# 01-main.net
KiCad netlist of a schematic drawn in EAGLE
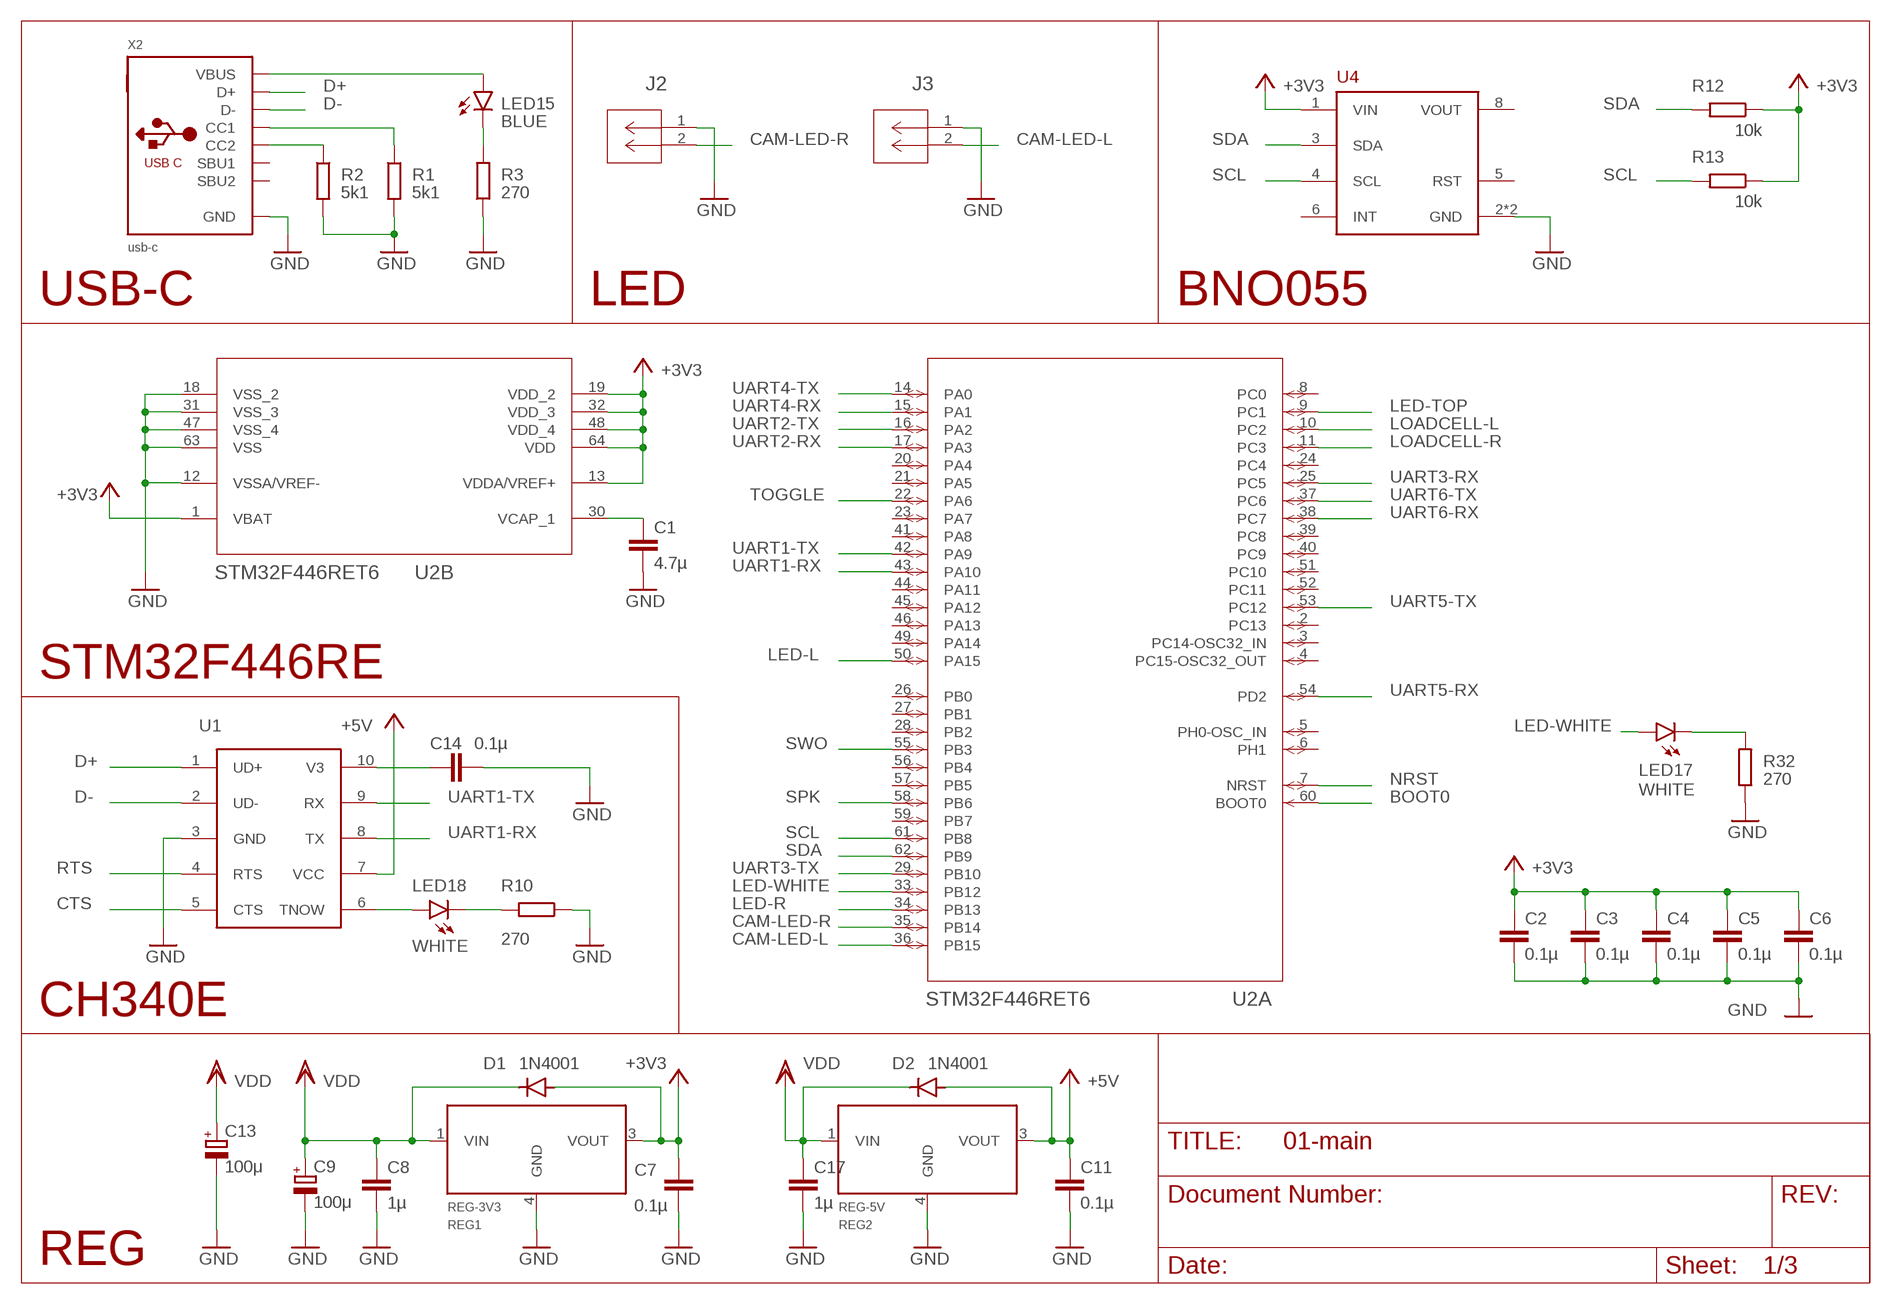
[diagram p0: schematic, sheet 1]
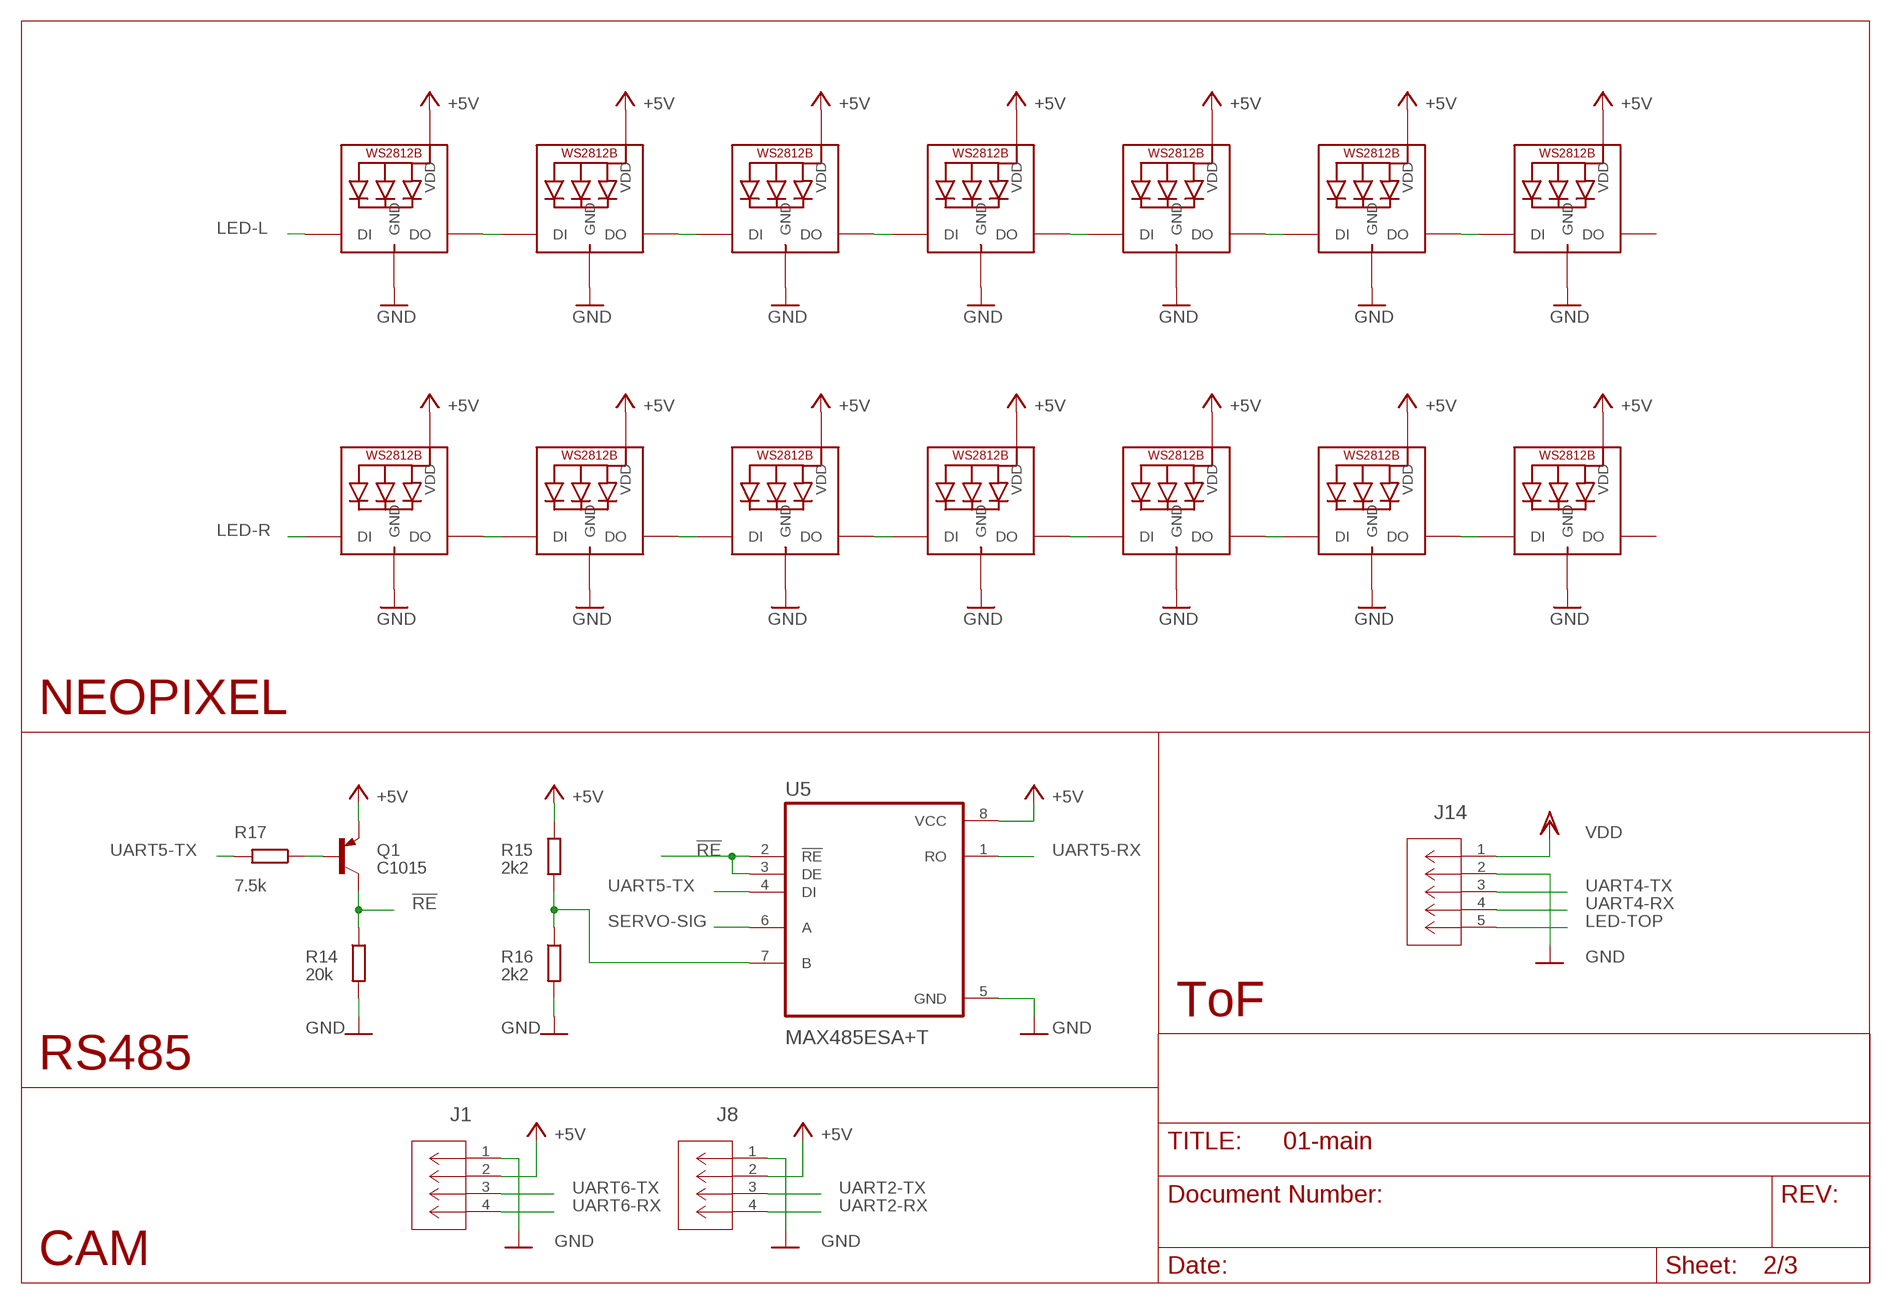
[diagram p1: schematic, sheet 2]
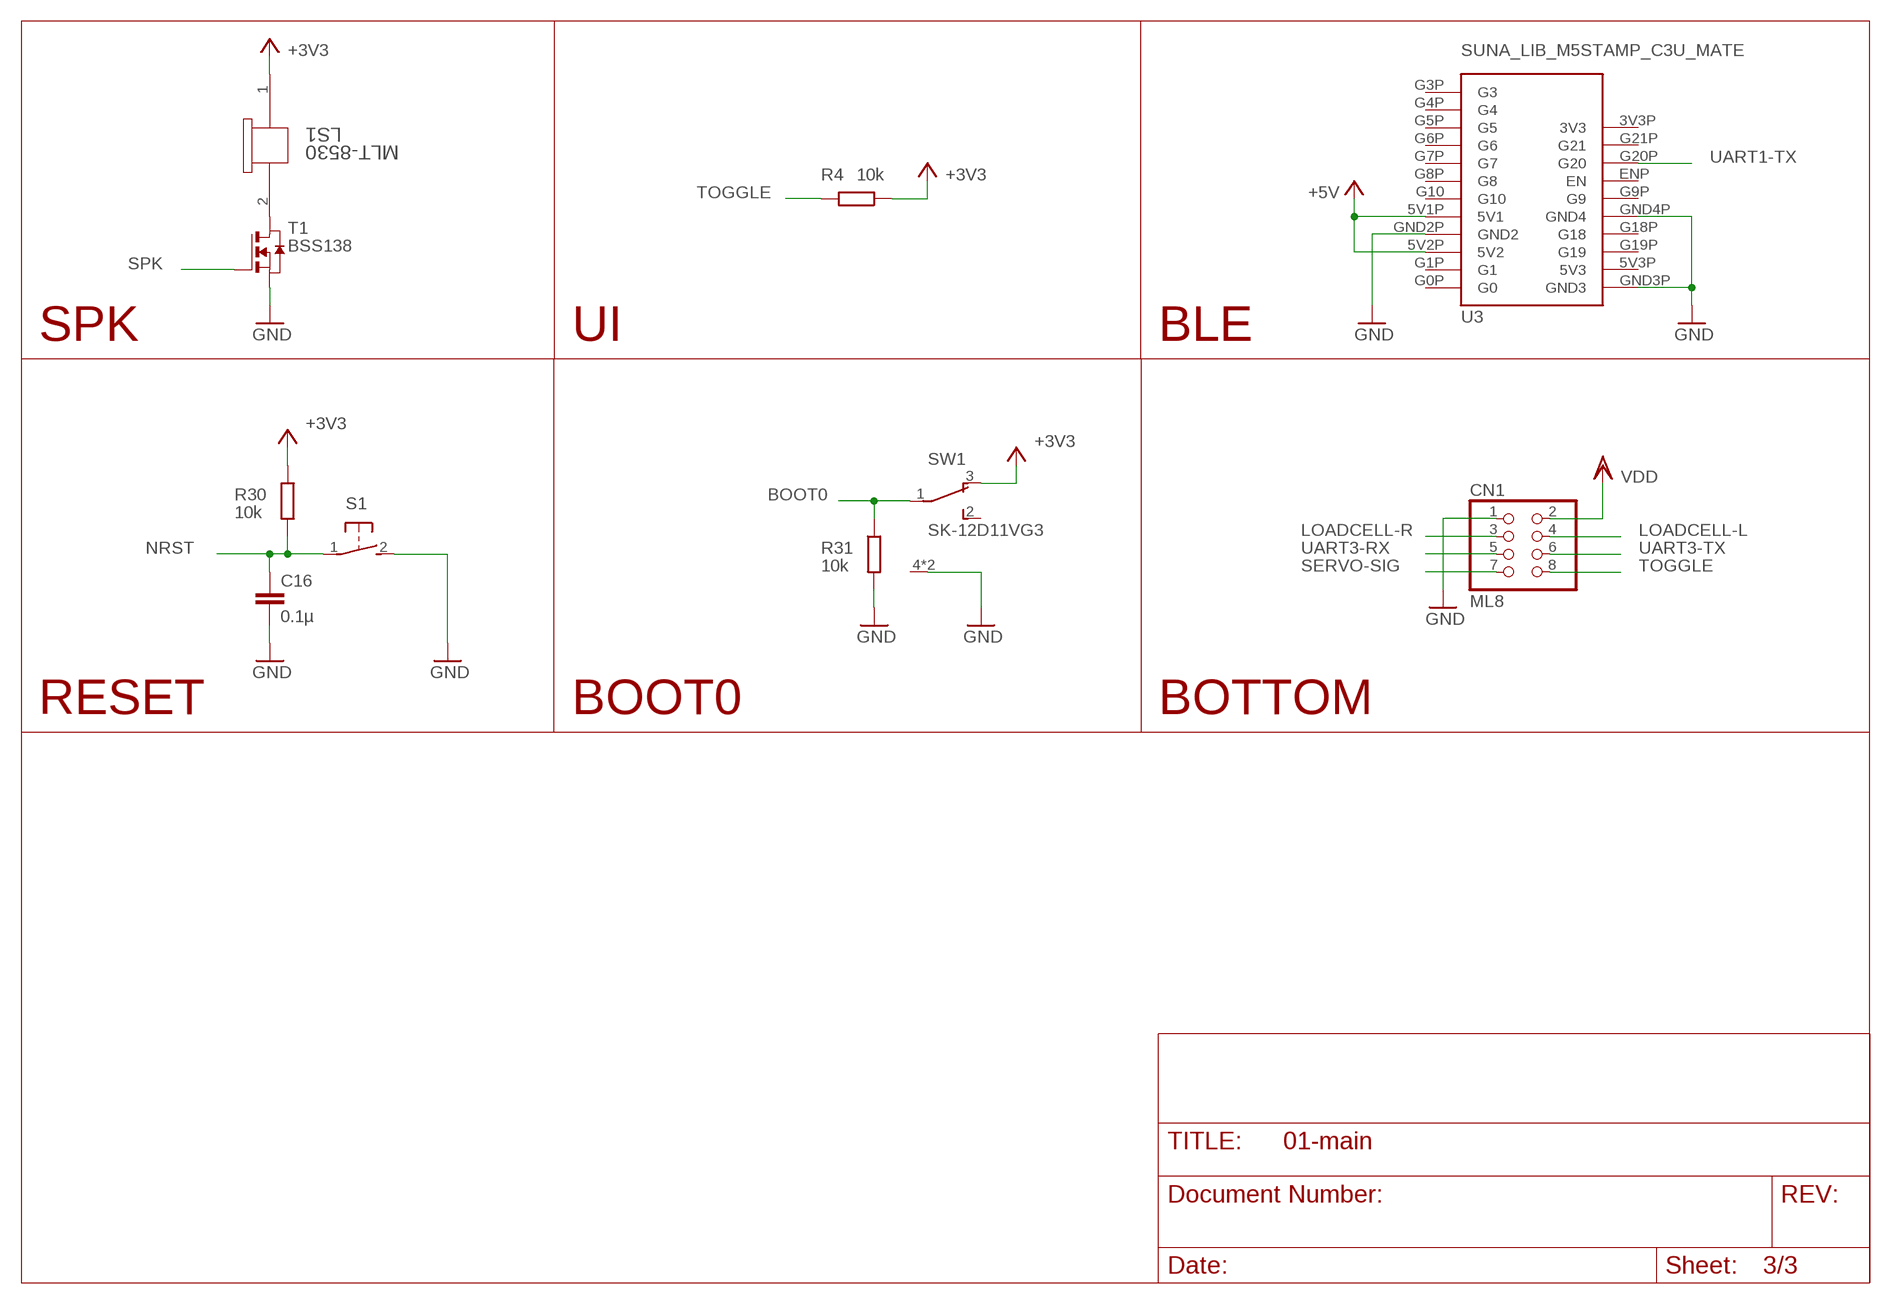
[diagram p2: schematic, sheet 3]

(export (version "E")
  (design (tool "Eeschema 10.0.6"))
  (components
    (comp (ref "J1")
      (value "22057045")
      (footprint "eagle-import:CON_22057045_MOL")
      (fields (field (name "COPYRIGHT") "Copyright (C) 2022 Ultra Librarian. All rights reserved."))
      (libsource (lib "eagle-import") (part "22057045"))
    )
    (comp (ref "J8")
      (value "22057045")
      (footprint "eagle-import:CON_22057045_MOL")
      (fields (field (name "COPYRIGHT") "Copyright (C) 2022 Ultra Librarian. All rights reserved."))
      (libsource (lib "eagle-import") (part "22057045"))
    )
    (comp (ref "J14")
      (value "22057055")
      (footprint "eagle-import:CON_22057055_MOL")
      (fields (field (name "COPYRIGHT") "Copyright (C) 2022 Ultra Librarian. All rights reserved."))
      (libsource (lib "eagle-import") (part "22057055"))
    )
    (comp (ref "LED1")
      (value "WS2812B_2020")
      (footprint "eagle-import:WS2812B_2020")
      (libsource (lib "eagle-import") (part "WS2812B_2020"))
    )
    (comp (ref "LED2")
      (value "WS2812B_2020")
      (footprint "eagle-import:WS2812B_2020")
      (libsource (lib "eagle-import") (part "WS2812B_2020"))
    )
    (comp (ref "LED3")
      (value "WS2812B_2020")
      (footprint "eagle-import:WS2812B_2020")
      (libsource (lib "eagle-import") (part "WS2812B_2020"))
    )
    (comp (ref "LED4")
      (value "WS2812B_2020")
      (footprint "eagle-import:WS2812B_2020")
      (libsource (lib "eagle-import") (part "WS2812B_2020"))
    )
    (comp (ref "LED5")
      (value "WS2812B_2020")
      (footprint "eagle-import:WS2812B_2020")
      (libsource (lib "eagle-import") (part "WS2812B_2020"))
    )
    (comp (ref "LED6")
      (value "WS2812B_2020")
      (footprint "eagle-import:WS2812B_2020")
      (libsource (lib "eagle-import") (part "WS2812B_2020"))
    )
    (comp (ref "LED7")
      (value "WS2812B_2020")
      (footprint "eagle-import:WS2812B_2020")
      (libsource (lib "eagle-import") (part "WS2812B_2020"))
    )
    (comp (ref "LED8")
      (value "WS2812B_2020")
      (footprint "eagle-import:WS2812B_2020")
      (libsource (lib "eagle-import") (part "WS2812B_2020"))
    )
    (comp (ref "LED9")
      (value "WS2812B_2020")
      (footprint "eagle-import:WS2812B_2020")
      (libsource (lib "eagle-import") (part "WS2812B_2020"))
    )
    (comp (ref "LED10")
      (value "WS2812B_2020")
      (footprint "eagle-import:WS2812B_2020")
      (libsource (lib "eagle-import") (part "WS2812B_2020"))
    )
    (comp (ref "LED11")
      (value "WS2812B_2020")
      (footprint "eagle-import:WS2812B_2020")
      (libsource (lib "eagle-import") (part "WS2812B_2020"))
    )
    (comp (ref "LED12")
      (value "WS2812B_2020")
      (footprint "eagle-import:WS2812B_2020")
      (libsource (lib "eagle-import") (part "WS2812B_2020"))
    )
    (comp (ref "LED13")
      (value "WS2812B_2020")
      (footprint "eagle-import:WS2812B_2020")
      (libsource (lib "eagle-import") (part "WS2812B_2020"))
    )
    (comp (ref "LED14")
      (value "WS2812B_2020")
      (footprint "eagle-import:WS2812B_2020")
      (libsource (lib "eagle-import") (part "WS2812B_2020"))
    )
    (comp (ref "Q1")
      (value "C1015")
      (footprint "eagle-import:SOT23")
      (libsource (lib "eagle-import") (part "BCX71SMD"))
    )
    (comp (ref "R14")
      (value "20k")
      (footprint "eagle-import:R0402")
      (libsource (lib "eagle-import") (part "R-EU_R0402"))
    )
    (comp (ref "R15")
      (value "2k2")
      (footprint "eagle-import:R0402")
      (libsource (lib "eagle-import") (part "R-EU_R0402"))
    )
    (comp (ref "R16")
      (value "2k2")
      (footprint "eagle-import:R0402")
      (libsource (lib "eagle-import") (part "R-EU_R0402"))
    )
    (comp (ref "R17")
      (value "7.5k")
      (footprint "eagle-import:R0402")
      (libsource (lib "eagle-import") (part "R-EU_R0402"))
    )
    (comp (ref "U5")
      (value "MAX485ESA+T")
      (footprint "eagle-import:SOIC127P600X175-8N")
      (fields (field (name "MF") "Maxim Integrated") (field (name "MP") "MAX485ESA"))
      (libsource (lib "eagle-import") (part "MAX485ESA+T"))
    )
    (comp (ref "C1")
      (value "4.7µ")
      (footprint "eagle-import:C0603")
      (libsource (lib "eagle-import") (part "C-EUC0603"))
    )
    (comp (ref "C2")
      (value "0.1µ")
      (footprint "eagle-import:C0603")
      (libsource (lib "eagle-import") (part "C-EUC0603"))
    )
    (comp (ref "C3")
      (value "0.1µ")
      (footprint "eagle-import:C0603")
      (libsource (lib "eagle-import") (part "C-EUC0603"))
    )
    (comp (ref "C4")
      (value "0.1µ")
      (footprint "eagle-import:C0603")
      (libsource (lib "eagle-import") (part "C-EUC0603"))
    )
    (comp (ref "C5")
      (value "0.1µ")
      (footprint "eagle-import:C0603")
      (libsource (lib "eagle-import") (part "C-EUC0603"))
    )
    (comp (ref "C6")
      (value "0.1µ")
      (footprint "eagle-import:C0603")
      (libsource (lib "eagle-import") (part "C-EUC0603"))
    )
    (comp (ref "C7")
      (value "0.1µ")
      (footprint "eagle-import:C0603")
      (libsource (lib "eagle-import") (part "C-EUC0603"))
    )
    (comp (ref "C8")
      (value "1µ")
      (footprint "eagle-import:C0603")
      (libsource (lib "eagle-import") (part "C-EUC0603"))
    )
    (comp (ref "C9")
      (value "100μ")
      (footprint "eagle-import:153CLV-0505")
      (libsource (lib "eagle-import") (part "CPOL-EU153CLV-0505"))
    )
    (comp (ref "C11")
      (value "0.1µ")
      (footprint "eagle-import:C0603")
      (libsource (lib "eagle-import") (part "C-EUC0603"))
    )
    (comp (ref "C13")
      (value "100μ")
      (footprint "eagle-import:153CLV-0505")
      (libsource (lib "eagle-import") (part "CPOL-EU153CLV-0505"))
    )
    (comp (ref "C14")
      (value "0.1µ")
      (footprint "eagle-import:C0603")
      (libsource (lib "eagle-import") (part "C-EUC0603"))
    )
    (comp (ref "C17")
      (value "1µ")
      (footprint "eagle-import:C0603")
      (libsource (lib "eagle-import") (part "C-EUC0603"))
    )
    (comp (ref "D1")
      (value "1N4001")
      (footprint "eagle-import:SMA-DO214AC")
      (libsource (lib "eagle-import") (part "GF1"))
    )
    (comp (ref "D2")
      (value "1N4001")
      (footprint "eagle-import:SMA-DO214AC")
      (libsource (lib "eagle-import") (part "GF1"))
    )
    (comp (ref "J2")
      (value "22057025")
      (footprint "eagle-import:CON_22057025_MOL")
      (fields (field (name "COPYRIGHT") "Copyright (C) 2022 Ultra Librarian. All rights reserved."))
      (libsource (lib "eagle-import") (part "22057025"))
    )
    (comp (ref "J3")
      (value "22057025")
      (footprint "eagle-import:CON_22057025_MOL")
      (fields (field (name "COPYRIGHT") "Copyright (C) 2022 Ultra Librarian. All rights reserved."))
      (libsource (lib "eagle-import") (part "22057025"))
    )
    (comp (ref "LED15")
      (value "BLUE")
      (footprint "eagle-import:SML0603")
      (libsource (lib "eagle-import") (part "LEDSML0603"))
    )
    (comp (ref "LED17")
      (value "WHITE")
      (footprint "eagle-import:SML0603")
      (libsource (lib "eagle-import") (part "LEDSML0603"))
    )
    (comp (ref "LED18")
      (value "WHITE")
      (footprint "eagle-import:SML0603")
      (libsource (lib "eagle-import") (part "LEDSML0603"))
    )
    (comp (ref "R1")
      (value "5k1")
      (footprint "eagle-import:R0402")
      (libsource (lib "eagle-import") (part "R-EU_R0402"))
    )
    (comp (ref "R2")
      (value "5k1")
      (footprint "eagle-import:R0402")
      (libsource (lib "eagle-import") (part "R-EU_R0402"))
    )
    (comp (ref "R3")
      (value "270")
      (footprint "eagle-import:R0402")
      (libsource (lib "eagle-import") (part "R-EU_R0402"))
    )
    (comp (ref "R10")
      (value "270")
      (footprint "eagle-import:R0402")
      (libsource (lib "eagle-import") (part "R-EU_R0402"))
    )
    (comp (ref "R12")
      (value "10k")
      (footprint "eagle-import:R0402")
      (libsource (lib "eagle-import") (part "R-EU_R0402"))
    )
    (comp (ref "R13")
      (value "10k")
      (footprint "eagle-import:R0402")
      (libsource (lib "eagle-import") (part "R-EU_R0402"))
    )
    (comp (ref "R32")
      (value "270")
      (footprint "eagle-import:R0402")
      (libsource (lib "eagle-import") (part "R-EU_R0402"))
    )
    (comp (ref "REG1")
      (value "REG-3V3")
      (footprint "eagle-import:MYPARTS_D-PAK_TO252AA")
      (libsource (lib "eagle-import") (part "MYPARTS_NJM7800S-REGULATOR"))
    )
    (comp (ref "REG2")
      (value "REG-5V")
      (footprint "eagle-import:MYPARTS_D-PAK_TO252AA")
      (libsource (lib "eagle-import") (part "MYPARTS_NJM7800S-REGULATOR"))
    )
    (comp (ref "U1")
      (value "CH340ESMD")
      (footprint "eagle-import:MSOP10")
      (libsource (lib "eagle-import") (part "CH340ESMD"))
    )
    (comp (ref "U2")
      (value "STM32F446RET6")
      (footprint "eagle-import:LQFP64-10X10MM")
      (fields (field (name "COPYRIGHT") "Copyright (C) 2022 Ultra Librarian. All rights reserved."))
      (libsource (lib "eagle-import") (part "STM32F446RET6"))
    )
    (comp (ref "U4")
      (value "BNO055")
      (footprint "eagle-import:SOCKET-08")
      (libsource (lib "eagle-import") (part "BNO055"))
    )
    (comp (ref "X2")
      (value "usb-c")
      (footprint "eagle-import:USB_C_CUSB31-CFM2AX-01-X")
      (libsource (lib "eagle-import") (part "USB_C"))
    )
    (comp (ref "C16")
      (value "0.1µ")
      (footprint "eagle-import:C0603")
      (libsource (lib "eagle-import") (part "C-EUC0603"))
    )
    (comp (ref "CN1")
      (value "ML8")
      (footprint "eagle-import:ML6L")
      (libsource (lib "eagle-import") (part "ML8"))
    )
    (comp (ref "LS1")
      (value "MLT-8530")
      (footprint "eagle-import:MLT-8530_JHE")
      (fields (field (name "COPYRIGHT") "Copyright (C) 2022 Ultra Librarian. All rights reserved."))
      (libsource (lib "eagle-import") (part "MLT-8530"))
    )
    (comp (ref "R4")
      (value "10k")
      (footprint "eagle-import:R0402")
      (libsource (lib "eagle-import") (part "R-EU_R0402"))
    )
    (comp (ref "R30")
      (value "10k")
      (footprint "eagle-import:R0402")
      (libsource (lib "eagle-import") (part "R-EU_R0402"))
    )
    (comp (ref "R31")
      (value "10k")
      (footprint "eagle-import:R0402")
      (libsource (lib "eagle-import") (part "R-EU_R0402"))
    )
    (comp (ref "S1")
      (value "31-XX")
      (footprint "eagle-import:B3F-31XX")
      (fields (field (name "MPN") "B3F-3100"))
      (libsource (lib "eagle-import") (part "31-XX"))
    )
    (comp (ref "SW1")
      (value "SK-12D11VG3")
      (footprint "eagle-import:SK-12D11VG3")
      (libsource (lib "eagle-import") (part "SK-12D11VG3"))
    )
    (comp (ref "T1")
      (value "BSS138")
      (footprint "eagle-import:SOT-23")
      (libsource (lib "eagle-import") (part "NMOSSOT23"))
    )
    (comp (ref "U3")
      (value "SUNA_LIB_M5STAMP_C3U_MATE")
      (footprint "eagle-import:SUNA_LIB_M5STAMPC3UMATE")
      (libsource (lib "eagle-import") (part "SUNA_LIB_M5STAMP_C3U_MATE"))
    )
  )
  (nets
    (net (code "1") (name "+3V3") (class "Default")
      (node (ref "C2") (pin "1") (pinfunction "1_1") (pintype "passive"))
      (node (ref "C3") (pin "1") (pinfunction "1_1") (pintype "passive"))
      (node (ref "C4") (pin "1") (pinfunction "1_1") (pintype "passive"))
      (node (ref "C5") (pin "1") (pinfunction "1_1") (pintype "passive"))
      (node (ref "C6") (pin "1") (pinfunction "1_1") (pintype "passive"))
      (node (ref "C7") (pin "1") (pinfunction "1_1") (pintype "passive"))
      (node (ref "D1") (pin "A") (pinfunction "A_A") (pintype "passive"))
      (node (ref "LS1") (pin "1") (pinfunction "1_1") (pintype "passive"))
      (node (ref "R12") (pin "1") (pinfunction "1_1") (pintype "passive"))
      (node (ref "R13") (pin "1") (pinfunction "1_1") (pintype "passive"))
      (node (ref "R30") (pin "1") (pinfunction "1_1") (pintype "passive"))
      (node (ref "R4") (pin "1") (pinfunction "1_1") (pintype "passive"))
      (node (ref "REG1") (pin "3") (pinfunction "VOUT_3") (pintype "passive"))
      (node (ref "SW1") (pin "3") (pinfunction "O_3") (pintype "passive"))
      (node (ref "U2") (pin "1") (pinfunction "VBAT_1") (pintype "power_in"))
      (node (ref "U2") (pin "13") (pinfunction "VDDA/VREF+_13") (pintype "power_in"))
      (node (ref "U2") (pin "19") (pinfunction "VDD_2_19") (pintype "power_in"))
      (node (ref "U2") (pin "32") (pinfunction "VDD_3_32") (pintype "power_in"))
      (node (ref "U2") (pin "48") (pinfunction "VDD_4_48") (pintype "power_in"))
      (node (ref "U2") (pin "64") (pinfunction "VDD_64") (pintype "power_in"))
      (node (ref "U4") (pin "1") (pinfunction "VIN_1") (pintype "power_in"))
    )
    (net (code "2") (name "+5V") (class "Default")
      (node (ref "C11") (pin "1") (pinfunction "1_1") (pintype "passive"))
      (node (ref "D2") (pin "A") (pinfunction "A_A") (pintype "passive"))
      (node (ref "J1") (pin "2") (pinfunction "2_2") (pintype "passive"))
      (node (ref "J8") (pin "2") (pinfunction "2_2") (pintype "passive"))
      (node (ref "LED1") (pin "4") (pinfunction "VDD_4") (pintype "power_in"))
      (node (ref "LED10") (pin "4") (pinfunction "VDD_4") (pintype "power_in"))
      (node (ref "LED11") (pin "4") (pinfunction "VDD_4") (pintype "power_in"))
      (node (ref "LED12") (pin "4") (pinfunction "VDD_4") (pintype "power_in"))
      (node (ref "LED13") (pin "4") (pinfunction "VDD_4") (pintype "power_in"))
      (node (ref "LED14") (pin "4") (pinfunction "VDD_4") (pintype "power_in"))
      (node (ref "LED2") (pin "4") (pinfunction "VDD_4") (pintype "power_in"))
      (node (ref "LED3") (pin "4") (pinfunction "VDD_4") (pintype "power_in"))
      (node (ref "LED4") (pin "4") (pinfunction "VDD_4") (pintype "power_in"))
      (node (ref "LED5") (pin "4") (pinfunction "VDD_4") (pintype "power_in"))
      (node (ref "LED6") (pin "4") (pinfunction "VDD_4") (pintype "power_in"))
      (node (ref "LED7") (pin "4") (pinfunction "VDD_4") (pintype "power_in"))
      (node (ref "LED8") (pin "4") (pinfunction "VDD_4") (pintype "power_in"))
      (node (ref "LED9") (pin "4") (pinfunction "VDD_4") (pintype "power_in"))
      (node (ref "Q1") (pin "2") (pinfunction "E_2") (pintype "passive"))
      (node (ref "R15") (pin "1") (pinfunction "1_1") (pintype "passive"))
      (node (ref "REG2") (pin "3") (pinfunction "VOUT_3") (pintype "passive"))
      (node (ref "U1") (pin "7") (pinfunction "VCC_7") (pintype "power_in"))
      (node (ref "U3") (pin "5V1P") (pinfunction "5V1_5V1P") (pintype "bidirectional"))
      (node (ref "U3") (pin "5V2P") (pinfunction "5V2_5V2P") (pintype "bidirectional"))
      (node (ref "U5") (pin "8") (pinfunction "VCC_8") (pintype "power_in"))
    )
    (net (code "3") (name "BOOT0") (class "Default")
      (node (ref "R31") (pin "1") (pinfunction "1_1") (pintype "passive"))
      (node (ref "SW1") (pin "1") (pinfunction "P_1") (pintype "passive"))
      (node (ref "U2") (pin "60") (pinfunction "BOOT0_60") (pintype "input"))
    )
    (net (code "4") (name "CAM-LED-L") (class "Default")
      (node (ref "J3") (pin "2") (pinfunction "2_2") (pintype "passive"))
      (node (ref "U2") (pin "36") (pinfunction "PB15_36") (pintype "bidirectional"))
    )
    (net (code "5") (name "CAM-LED-R") (class "Default")
      (node (ref "J2") (pin "2") (pinfunction "2_2") (pintype "passive"))
      (node (ref "U2") (pin "35") (pinfunction "PB14_35") (pintype "bidirectional"))
    )
    (net (code "6") (name "CTS") (class "Default")
      (node (ref "U1") (pin "5") (pinfunction "CTS_5") (pintype "input"))
    )
    (net (code "7") (name "D+") (class "Default")
      (node (ref "U1") (pin "1") (pinfunction "UD+_1") (pintype "bidirectional"))
      (node (ref "X2") (pin "A6") (pinfunction "D+_A6") (pintype "bidirectional"))
      (node (ref "X2") (pin "B6") (pinfunction "D+_B6") (pintype "bidirectional"))
    )
    (net (code "8") (name "D-") (class "Default")
      (node (ref "U1") (pin "2") (pinfunction "UD-_2") (pintype "bidirectional"))
      (node (ref "X2") (pin "A7") (pinfunction "D-_A7") (pintype "bidirectional"))
      (node (ref "X2") (pin "B7") (pinfunction "D-_B7") (pintype "bidirectional"))
    )
    (net (code "9") (name "GND") (class "Default")
      (node (ref "C1") (pin "2") (pinfunction "2_2") (pintype "passive"))
      (node (ref "C11") (pin "2") (pinfunction "2_2") (pintype "passive"))
      (node (ref "C13") (pin "-") (pinfunction "-_-") (pintype "passive"))
      (node (ref "C14") (pin "2") (pinfunction "2_2") (pintype "passive"))
      (node (ref "C16") (pin "2") (pinfunction "2_2") (pintype "passive"))
      (node (ref "C17") (pin "2") (pinfunction "2_2") (pintype "passive"))
      (node (ref "C2") (pin "2") (pinfunction "2_2") (pintype "passive"))
      (node (ref "C3") (pin "2") (pinfunction "2_2") (pintype "passive"))
      (node (ref "C4") (pin "2") (pinfunction "2_2") (pintype "passive"))
      (node (ref "C5") (pin "2") (pinfunction "2_2") (pintype "passive"))
      (node (ref "C6") (pin "2") (pinfunction "2_2") (pintype "passive"))
      (node (ref "C7") (pin "2") (pinfunction "2_2") (pintype "passive"))
      (node (ref "C8") (pin "2") (pinfunction "2_2") (pintype "passive"))
      (node (ref "C9") (pin "-") (pinfunction "-_-") (pintype "passive"))
      (node (ref "CN1") (pin "1") (pinfunction "1_1") (pintype "passive"))
      (node (ref "J1") (pin "1") (pinfunction "1_1") (pintype "passive"))
      (node (ref "J14") (pin "2") (pinfunction "2_2") (pintype "passive"))
      (node (ref "J2") (pin "1") (pinfunction "1_1") (pintype "passive"))
      (node (ref "J3") (pin "1") (pinfunction "1_1") (pintype "passive"))
      (node (ref "J8") (pin "1") (pinfunction "1_1") (pintype "passive"))
      (node (ref "LED1") (pin "2") (pinfunction "GND_2") (pintype "power_in"))
      (node (ref "LED10") (pin "2") (pinfunction "GND_2") (pintype "power_in"))
      (node (ref "LED11") (pin "2") (pinfunction "GND_2") (pintype "power_in"))
      (node (ref "LED12") (pin "2") (pinfunction "GND_2") (pintype "power_in"))
      (node (ref "LED13") (pin "2") (pinfunction "GND_2") (pintype "power_in"))
      (node (ref "LED14") (pin "2") (pinfunction "GND_2") (pintype "power_in"))
      (node (ref "LED2") (pin "2") (pinfunction "GND_2") (pintype "power_in"))
      (node (ref "LED3") (pin "2") (pinfunction "GND_2") (pintype "power_in"))
      (node (ref "LED4") (pin "2") (pinfunction "GND_2") (pintype "power_in"))
      (node (ref "LED5") (pin "2") (pinfunction "GND_2") (pintype "power_in"))
      (node (ref "LED6") (pin "2") (pinfunction "GND_2") (pintype "power_in"))
      (node (ref "LED7") (pin "2") (pinfunction "GND_2") (pintype "power_in"))
      (node (ref "LED8") (pin "2") (pinfunction "GND_2") (pintype "power_in"))
      (node (ref "LED9") (pin "2") (pinfunction "GND_2") (pintype "power_in"))
      (node (ref "R1") (pin "2") (pinfunction "2_2") (pintype "passive"))
      (node (ref "R10") (pin "1") (pinfunction "1_1") (pintype "passive"))
      (node (ref "R14") (pin "2") (pinfunction "2_2") (pintype "passive"))
      (node (ref "R16") (pin "2") (pinfunction "2_2") (pintype "passive"))
      (node (ref "R2") (pin "2") (pinfunction "2_2") (pintype "passive"))
      (node (ref "R3") (pin "1") (pinfunction "1_1") (pintype "passive"))
      (node (ref "R31") (pin "2") (pinfunction "2_2") (pintype "passive"))
      (node (ref "R32") (pin "1") (pinfunction "1_1") (pintype "passive"))
      (node (ref "REG1") (pin "4") (pinfunction "GND_4") (pintype "passive"))
      (node (ref "REG2") (pin "4") (pinfunction "GND_4") (pintype "passive"))
      (node (ref "S1") (pin "2") (pinfunction "S_2") (pintype "passive"))
      (node (ref "SW1") (pin "4") (pinfunction "CASE_4") (pintype "bidirectional"))
      (node (ref "SW1") (pin "5") (pinfunction "CASE_5") (pintype "bidirectional"))
      (node (ref "T1") (pin "2") (pinfunction "S_2") (pintype "passive"))
      (node (ref "U1") (pin "3") (pinfunction "GND_3") (pintype "power_in"))
      (node (ref "U2") (pin "12") (pinfunction "VSSA/VREF-_12") (pintype "power_in"))
      (node (ref "U2") (pin "18") (pinfunction "VSS_2_18") (pintype "power_in"))
      (node (ref "U2") (pin "31") (pinfunction "VSS_3_31") (pintype "power_in"))
      (node (ref "U2") (pin "47") (pinfunction "VSS_4_47") (pintype "power_in"))
      (node (ref "U2") (pin "63") (pinfunction "VSS_63") (pintype "power_in"))
      (node (ref "U3") (pin "GND2P") (pinfunction "GND2_GND2P") (pintype "bidirectional"))
      (node (ref "U3") (pin "GND3P") (pinfunction "GND3_GND3P") (pintype "bidirectional"))
      (node (ref "U3") (pin "GND4P") (pinfunction "GND4_GND4P") (pintype "bidirectional"))
      (node (ref "U4") (pin "2") (pinfunction "GND_2") (pintype "power_in"))
      (node (ref "U4") (pin "7") (pinfunction "GND_7") (pintype "power_in"))
      (node (ref "U5") (pin "5") (pinfunction "GND_5") (pintype "power_in"))
      (node (ref "X2") (pin "A1B12") (pinfunction "GND_A1B12") (pintype "power_in"))
      (node (ref "X2") (pin "B1A12") (pinfunction "GND_B1A12") (pintype "power_in"))
    )
    (net (code "10") (name "LED-L") (class "Default")
      (node (ref "LED1") (pin "3") (pinfunction "DI_3") (pintype "input"))
      (node (ref "U2") (pin "50") (pinfunction "PA15_50") (pintype "bidirectional"))
    )
    (net (code "11") (name "LED-R") (class "Default")
      (node (ref "LED8") (pin "3") (pinfunction "DI_3") (pintype "input"))
      (node (ref "U2") (pin "34") (pinfunction "PB13_34") (pintype "bidirectional"))
    )
    (net (code "12") (name "LED-TOP") (class "Default")
      (node (ref "J14") (pin "5") (pinfunction "5_5") (pintype "passive"))
      (node (ref "U2") (pin "9") (pinfunction "PC1_9") (pintype "bidirectional"))
    )
    (net (code "13") (name "LED-WHITE") (class "Default")
      (node (ref "LED17") (pin "A") (pinfunction "A_A") (pintype "passive"))
      (node (ref "U2") (pin "33") (pinfunction "PB12_33") (pintype "bidirectional"))
    )
    (net (code "14") (name "LOADCELL-L") (class "Default")
      (node (ref "CN1") (pin "4") (pinfunction "4_4") (pintype "passive"))
      (node (ref "U2") (pin "10") (pinfunction "PC2_10") (pintype "bidirectional"))
    )
    (net (code "15") (name "LOADCELL-R") (class "Default")
      (node (ref "CN1") (pin "3") (pinfunction "3_3") (pintype "passive"))
      (node (ref "U2") (pin "11") (pinfunction "PC3_11") (pintype "bidirectional"))
    )
    (net (code "16") (name "NRST") (class "Default")
      (node (ref "C16") (pin "1") (pinfunction "1_1") (pintype "passive"))
      (node (ref "R30") (pin "2") (pinfunction "2_2") (pintype "passive"))
      (node (ref "S1") (pin "1") (pinfunction "P_1") (pintype "passive"))
      (node (ref "U2") (pin "7") (pinfunction "NRST_7") (pintype "bidirectional"))
    )
    (net (code "17") (name "Net-(LED1-DO)") (class "Default")
      (node (ref "LED1") (pin "1") (pinfunction "DO_1") (pintype "output"))
      (node (ref "LED2") (pin "3") (pinfunction "DI_3") (pintype "input"))
    )
    (net (code "18") (name "Net-(LED2-DO)") (class "Default")
      (node (ref "LED2") (pin "1") (pinfunction "DO_1") (pintype "output"))
      (node (ref "LED3") (pin "3") (pinfunction "DI_3") (pintype "input"))
    )
    (net (code "19") (name "Net-(LED3-DO)") (class "Default")
      (node (ref "LED3") (pin "1") (pinfunction "DO_1") (pintype "output"))
      (node (ref "LED4") (pin "3") (pinfunction "DI_3") (pintype "input"))
    )
    (net (code "20") (name "Net-(LED4-DO)") (class "Default")
      (node (ref "LED4") (pin "1") (pinfunction "DO_1") (pintype "output"))
      (node (ref "LED5") (pin "3") (pinfunction "DI_3") (pintype "input"))
    )
    (net (code "21") (name "Net-(LED5-DO)") (class "Default")
      (node (ref "LED5") (pin "1") (pinfunction "DO_1") (pintype "output"))
      (node (ref "LED6") (pin "3") (pinfunction "DI_3") (pintype "input"))
    )
    (net (code "22") (name "Net-(LED6-DO)") (class "Default")
      (node (ref "LED6") (pin "1") (pinfunction "DO_1") (pintype "output"))
      (node (ref "LED7") (pin "3") (pinfunction "DI_3") (pintype "input"))
    )
    (net (code "23") (name "Net-(LED8-DO)") (class "Default")
      (node (ref "LED8") (pin "1") (pinfunction "DO_1") (pintype "output"))
      (node (ref "LED9") (pin "3") (pinfunction "DI_3") (pintype "input"))
    )
    (net (code "24") (name "Net-(LED10-DI)") (class "Default")
      (node (ref "LED10") (pin "3") (pinfunction "DI_3") (pintype "input"))
      (node (ref "LED9") (pin "1") (pinfunction "DO_1") (pintype "output"))
    )
    (net (code "25") (name "Net-(LED10-DO)") (class "Default")
      (node (ref "LED10") (pin "1") (pinfunction "DO_1") (pintype "output"))
      (node (ref "LED11") (pin "3") (pinfunction "DI_3") (pintype "input"))
    )
    (net (code "26") (name "Net-(LED11-DO)") (class "Default")
      (node (ref "LED11") (pin "1") (pinfunction "DO_1") (pintype "output"))
      (node (ref "LED12") (pin "3") (pinfunction "DI_3") (pintype "input"))
    )
    (net (code "27") (name "Net-(LED12-DO)") (class "Default")
      (node (ref "LED12") (pin "1") (pinfunction "DO_1") (pintype "output"))
      (node (ref "LED13") (pin "3") (pinfunction "DI_3") (pintype "input"))
    )
    (net (code "28") (name "Net-(LED13-DO)") (class "Default")
      (node (ref "LED13") (pin "1") (pinfunction "DO_1") (pintype "output"))
      (node (ref "LED14") (pin "3") (pinfunction "DI_3") (pintype "input"))
    )
    (net (code "29") (name "Net-(LED15-PadA)") (class "Default")
      (node (ref "LED15") (pin "A") (pinfunction "A_A") (pintype "passive"))
      (node (ref "X2") (pin "A4B9") (pinfunction "VBUS_A4B9") (pintype "power_in"))
      (node (ref "X2") (pin "B4A9") (pinfunction "VBUS_B4A9") (pintype "power_in"))
    )
    (net (code "30") (name "Net-(LED15-PadC)") (class "Default")
      (node (ref "LED15") (pin "C") (pinfunction "C_C") (pintype "passive"))
      (node (ref "R3") (pin "2") (pinfunction "2_2") (pintype "passive"))
    )
    (net (code "31") (name "Net-(LED17-PadC)") (class "Default")
      (node (ref "LED17") (pin "C") (pinfunction "C_C") (pintype "passive"))
      (node (ref "R32") (pin "2") (pinfunction "2_2") (pintype "passive"))
    )
    (net (code "32") (name "Net-(LED18-PadC)") (class "Default")
      (node (ref "LED18") (pin "C") (pinfunction "C_C") (pintype "passive"))
      (node (ref "R10") (pin "2") (pinfunction "2_2") (pintype "passive"))
    )
    (net (code "33") (name "Net-(Q1-B)") (class "Default")
      (node (ref "Q1") (pin "1") (pinfunction "B_1") (pintype "passive"))
      (node (ref "R17") (pin "1") (pinfunction "1_1") (pintype "passive"))
    )
    (net (code "34") (name "Net-(T1-D)") (class "Default")
      (node (ref "LS1") (pin "2") (pinfunction "2_2") (pintype "passive"))
      (node (ref "T1") (pin "1") (pinfunction "D_1") (pintype "passive"))
    )
    (net (code "35") (name "Net-(U1-TNOW)") (class "Default")
      (node (ref "LED18") (pin "A") (pinfunction "A_A") (pintype "passive"))
      (node (ref "U1") (pin "6") (pinfunction "TNOW_6") (pintype "output"))
    )
    (net (code "36") (name "Net-(U1-V3)") (class "Default")
      (node (ref "C14") (pin "1") (pinfunction "1_1") (pintype "passive"))
      (node (ref "U1") (pin "10") (pinfunction "V3_10") (pintype "power_in"))
    )
    (net (code "37") (name "Net-(U2B-VCAP_1)") (class "Default")
      (node (ref "C1") (pin "1") (pinfunction "1_1") (pintype "passive"))
      (node (ref "U2") (pin "30") (pinfunction "VCAP_1_30") (pintype "power_in"))
    )
    (net (code "38") (name "Net-(U5-B)") (class "Default")
      (node (ref "R15") (pin "2") (pinfunction "2_2") (pintype "passive"))
      (node (ref "R16") (pin "1") (pinfunction "1_1") (pintype "passive"))
      (node (ref "U5") (pin "7") (pinfunction "B_7") (pintype "bidirectional"))
    )
    (net (code "39") (name "Net-(X2-CC1)") (class "Default")
      (node (ref "R1") (pin "1") (pinfunction "1_1") (pintype "passive"))
      (node (ref "X2") (pin "A5") (pinfunction "CC1_A5") (pintype "bidirectional"))
    )
    (net (code "40") (name "Net-(X2-CC2)") (class "Default")
      (node (ref "R2") (pin "1") (pinfunction "1_1") (pintype "passive"))
      (node (ref "X2") (pin "B5") (pinfunction "CC2_B5") (pintype "bidirectional"))
    )
    (net (code "41") (name "RTS") (class "Default")
      (node (ref "U1") (pin "4") (pinfunction "RTS_4") (pintype "output"))
    )
    (net (code "42") (name "SCL") (class "Default")
      (node (ref "R13") (pin "2") (pinfunction "2_2") (pintype "passive"))
      (node (ref "U2") (pin "61") (pinfunction "PB8_61") (pintype "bidirectional"))
      (node (ref "U4") (pin "4") (pinfunction "SCL_4") (pintype "bidirectional"))
    )
    (net (code "43") (name "SDA") (class "Default")
      (node (ref "R12") (pin "2") (pinfunction "2_2") (pintype "passive"))
      (node (ref "U2") (pin "62") (pinfunction "PB9_62") (pintype "bidirectional"))
      (node (ref "U4") (pin "3") (pinfunction "SDA_3") (pintype "bidirectional"))
    )
    (net (code "44") (name "SERVO-SIG") (class "Default")
      (node (ref "CN1") (pin "7") (pinfunction "7_7") (pintype "passive"))
      (node (ref "U5") (pin "6") (pinfunction "A_6") (pintype "bidirectional"))
    )
    (net (code "45") (name "SPK") (class "Default")
      (node (ref "T1") (pin "3") (pinfunction "G_3") (pintype "passive"))
      (node (ref "U2") (pin "58") (pinfunction "PB6_58") (pintype "bidirectional"))
    )
    (net (code "46") (name "SWO") (class "Default")
      (node (ref "U2") (pin "55") (pinfunction "PB3_55") (pintype "bidirectional"))
    )
    (net (code "47") (name "TOGGLE") (class "Default")
      (node (ref "CN1") (pin "8") (pinfunction "8_8") (pintype "passive"))
      (node (ref "R4") (pin "2") (pinfunction "2_2") (pintype "passive"))
      (node (ref "U2") (pin "22") (pinfunction "PA6_22") (pintype "bidirectional"))
    )
    (net (code "48") (name "UART1-RX") (class "Default")
      (node (ref "U1") (pin "8") (pinfunction "TX_8") (pintype "output"))
      (node (ref "U2") (pin "43") (pinfunction "PA10_43") (pintype "bidirectional"))
    )
    (net (code "49") (name "UART1-TX") (class "Default")
      (node (ref "U1") (pin "9") (pinfunction "RX_9") (pintype "input"))
      (node (ref "U2") (pin "42") (pinfunction "PA9_42") (pintype "bidirectional"))
      (node (ref "U3") (pin "G20P") (pinfunction "G20_G20P") (pintype "bidirectional"))
    )
    (net (code "50") (name "UART2-RX") (class "Default")
      (node (ref "J8") (pin "4") (pinfunction "4_4") (pintype "passive"))
      (node (ref "U2") (pin "17") (pinfunction "PA3_17") (pintype "bidirectional"))
    )
    (net (code "51") (name "UART2-TX") (class "Default")
      (node (ref "J8") (pin "3") (pinfunction "3_3") (pintype "passive"))
      (node (ref "U2") (pin "16") (pinfunction "PA2_16") (pintype "bidirectional"))
    )
    (net (code "52") (name "UART3-RX") (class "Default")
      (node (ref "CN1") (pin "5") (pinfunction "5_5") (pintype "passive"))
      (node (ref "U2") (pin "25") (pinfunction "PC5_25") (pintype "bidirectional"))
    )
    (net (code "53") (name "UART3-TX") (class "Default")
      (node (ref "CN1") (pin "6") (pinfunction "6_6") (pintype "passive"))
      (node (ref "U2") (pin "29") (pinfunction "PB10_29") (pintype "bidirectional"))
    )
    (net (code "54") (name "UART4-RX") (class "Default")
      (node (ref "J14") (pin "4") (pinfunction "4_4") (pintype "passive"))
      (node (ref "U2") (pin "15") (pinfunction "PA1_15") (pintype "bidirectional"))
    )
    (net (code "55") (name "UART4-TX") (class "Default")
      (node (ref "J14") (pin "3") (pinfunction "3_3") (pintype "passive"))
      (node (ref "U2") (pin "14") (pinfunction "PA0_14") (pintype "bidirectional"))
    )
    (net (code "56") (name "UART5-RX") (class "Default")
      (node (ref "U2") (pin "54") (pinfunction "PD2_54") (pintype "bidirectional"))
      (node (ref "U5") (pin "1") (pinfunction "RO_1") (pintype "output"))
    )
    (net (code "57") (name "UART5-TX") (class "Default")
      (node (ref "R17") (pin "2") (pinfunction "2_2") (pintype "passive"))
      (node (ref "U2") (pin "53") (pinfunction "PC12_53") (pintype "bidirectional"))
      (node (ref "U5") (pin "4") (pinfunction "DI_4") (pintype "input"))
    )
    (net (code "58") (name "UART6-RX") (class "Default")
      (node (ref "J1") (pin "4") (pinfunction "4_4") (pintype "passive"))
      (node (ref "U2") (pin "38") (pinfunction "PC7_38") (pintype "bidirectional"))
    )
    (net (code "59") (name "UART6-TX") (class "Default")
      (node (ref "J1") (pin "3") (pinfunction "3_3") (pintype "passive"))
      (node (ref "U2") (pin "37") (pinfunction "PC6_37") (pintype "bidirectional"))
    )
    (net (code "60") (name "VDD") (class "Default")
      (node (ref "C13") (pin "+") (pinfunction "+_+") (pintype "passive"))
      (node (ref "C17") (pin "1") (pinfunction "1_1") (pintype "passive"))
      (node (ref "C8") (pin "1") (pinfunction "1_1") (pintype "passive"))
      (node (ref "C9") (pin "+") (pinfunction "+_+") (pintype "passive"))
      (node (ref "CN1") (pin "2") (pinfunction "2_2") (pintype "passive"))
      (node (ref "D1") (pin "K") (pinfunction "C_K") (pintype "passive"))
      (node (ref "D2") (pin "K") (pinfunction "C_K") (pintype "passive"))
      (node (ref "J14") (pin "1") (pinfunction "1_1") (pintype "passive"))
      (node (ref "REG1") (pin "1") (pinfunction "VIN_1") (pintype "passive"))
      (node (ref "REG2") (pin "1") (pinfunction "VIN_1") (pintype "passive"))
    )
    (net (code "61") (name "VOUT") (class "Default")
      (node (ref "U4") (pin "8") (pinfunction "VOUT_8") (pintype "power_in"))
    )
    (net (code "62") (name "unconnected-(LED7-DO-Pad1)") (class "Default")
      (node (ref "LED7") (pin "1") (pinfunction "DO_1") (pintype "output"))
    )
    (net (code "63") (name "unconnected-(LED14-DO-Pad1)") (class "Default")
      (node (ref "LED14") (pin "1") (pinfunction "DO_1") (pintype "output"))
    )
    (net (code "64") (name "unconnected-(SW1-S-Pad2)") (class "Default")
      (node (ref "SW1") (pin "2") (pinfunction "S_2") (pintype "passive"))
    )
    (net (code "65") (name "unconnected-(U2A-PA4-Pad20)") (class "Default")
      (node (ref "U2") (pin "20") (pinfunction "PA4_20") (pintype "bidirectional"))
    )
    (net (code "66") (name "unconnected-(U2A-PA5-Pad21)") (class "Default")
      (node (ref "U2") (pin "21") (pinfunction "PA5_21") (pintype "bidirectional"))
    )
    (net (code "67") (name "unconnected-(U2A-PA7-Pad23)") (class "Default")
      (node (ref "U2") (pin "23") (pinfunction "PA7_23") (pintype "bidirectional"))
    )
    (net (code "68") (name "unconnected-(U2A-PA8-Pad41)") (class "Default")
      (node (ref "U2") (pin "41") (pinfunction "PA8_41") (pintype "bidirectional"))
    )
    (net (code "69") (name "unconnected-(U2A-PA11-Pad44)") (class "Default")
      (node (ref "U2") (pin "44") (pinfunction "PA11_44") (pintype "bidirectional"))
    )
    (net (code "70") (name "unconnected-(U2A-PA12-Pad45)") (class "Default")
      (node (ref "U2") (pin "45") (pinfunction "PA12_45") (pintype "bidirectional"))
    )
    (net (code "71") (name "unconnected-(U2A-PA13-Pad46)") (class "Default")
      (node (ref "U2") (pin "46") (pinfunction "PA13_46") (pintype "bidirectional"))
    )
    (net (code "72") (name "unconnected-(U2A-PA14-Pad49)") (class "Default")
      (node (ref "U2") (pin "49") (pinfunction "PA14_49") (pintype "bidirectional"))
    )
    (net (code "73") (name "unconnected-(U2A-PB0-Pad26)") (class "Default")
      (node (ref "U2") (pin "26") (pinfunction "PB0_26") (pintype "bidirectional"))
    )
    (net (code "74") (name "unconnected-(U2A-PB1-Pad27)") (class "Default")
      (node (ref "U2") (pin "27") (pinfunction "PB1_27") (pintype "bidirectional"))
    )
    (net (code "75") (name "unconnected-(U2A-PB2-Pad28)") (class "Default")
      (node (ref "U2") (pin "28") (pinfunction "PB2_28") (pintype "bidirectional"))
    )
    (net (code "76") (name "unconnected-(U2A-PB4-Pad56)") (class "Default")
      (node (ref "U2") (pin "56") (pinfunction "PB4_56") (pintype "bidirectional"))
    )
    (net (code "77") (name "unconnected-(U2A-PB5-Pad57)") (class "Default")
      (node (ref "U2") (pin "57") (pinfunction "PB5_57") (pintype "bidirectional"))
    )
    (net (code "78") (name "unconnected-(U2A-PB7-Pad59)") (class "Default")
      (node (ref "U2") (pin "59") (pinfunction "PB7_59") (pintype "bidirectional"))
    )
    (net (code "79") (name "unconnected-(U2A-PC0-Pad8)") (class "Default")
      (node (ref "U2") (pin "8") (pinfunction "PC0_8") (pintype "bidirectional"))
    )
    (net (code "80") (name "unconnected-(U2A-PC4-Pad24)") (class "Default")
      (node (ref "U2") (pin "24") (pinfunction "PC4_24") (pintype "bidirectional"))
    )
    (net (code "81") (name "unconnected-(U2A-PC8-Pad39)") (class "Default")
      (node (ref "U2") (pin "39") (pinfunction "PC8_39") (pintype "bidirectional"))
    )
    (net (code "82") (name "unconnected-(U2A-PC9-Pad40)") (class "Default")
      (node (ref "U2") (pin "40") (pinfunction "PC9_40") (pintype "bidirectional"))
    )
    (net (code "83") (name "unconnected-(U2A-PC10-Pad51)") (class "Default")
      (node (ref "U2") (pin "51") (pinfunction "PC10_51") (pintype "bidirectional"))
    )
    (net (code "84") (name "unconnected-(U2A-PC11-Pad52)") (class "Default")
      (node (ref "U2") (pin "52") (pinfunction "PC11_52") (pintype "bidirectional"))
    )
    (net (code "85") (name "unconnected-(U2A-PC13-Pad2)") (class "Default")
      (node (ref "U2") (pin "2") (pinfunction "PC13_2") (pintype "bidirectional"))
    )
    (net (code "86") (name "unconnected-(U2A-PC14-OSC32_IN-Pad3)") (class "Default")
      (node (ref "U2") (pin "3") (pinfunction "PC14-OSC32_IN_3") (pintype "bidirectional"))
    )
    (net (code "87") (name "unconnected-(U2A-PC15-OSC32_OUT-Pad4)") (class "Default")
      (node (ref "U2") (pin "4") (pinfunction "PC15-OSC32_OUT_4") (pintype "bidirectional"))
    )
    (net (code "88") (name "unconnected-(U2A-PH0-OSC_IN-Pad5)") (class "Default")
      (node (ref "U2") (pin "5") (pinfunction "PH0-OSC_IN_5") (pintype "bidirectional"))
    )
    (net (code "89") (name "unconnected-(U2A-PH1-Pad6)") (class "Default")
      (node (ref "U2") (pin "6") (pinfunction "PH1_6") (pintype "bidirectional"))
    )
    (net (code "90") (name "unconnected-(U3-3V3-Pad3V3P)") (class "Default")
      (node (ref "U3") (pin "3V3P") (pinfunction "3V3_3V3P") (pintype "bidirectional"))
    )
    (net (code "91") (name "unconnected-(U3-5V3-Pad5V3P)") (class "Default")
      (node (ref "U3") (pin "5V3P") (pinfunction "5V3_5V3P") (pintype "bidirectional"))
    )
    (net (code "92") (name "unconnected-(U3-EN-PadENP)") (class "Default")
      (node (ref "U3") (pin "ENP") (pinfunction "EN_ENP") (pintype "bidirectional"))
    )
    (net (code "93") (name "unconnected-(U3-G0-PadG0P)") (class "Default")
      (node (ref "U3") (pin "G0P") (pinfunction "G0_G0P") (pintype "bidirectional"))
    )
    (net (code "94") (name "unconnected-(U3-G1-PadG1P)") (class "Default")
      (node (ref "U3") (pin "G1P") (pinfunction "G1_G1P") (pintype "bidirectional"))
    )
    (net (code "95") (name "unconnected-(U3-G3-PadG3P)") (class "Default")
      (node (ref "U3") (pin "G3P") (pinfunction "G3_G3P") (pintype "bidirectional"))
    )
    (net (code "96") (name "unconnected-(U3-G4-PadG4P)") (class "Default")
      (node (ref "U3") (pin "G4P") (pinfunction "G4_G4P") (pintype "bidirectional"))
    )
    (net (code "97") (name "unconnected-(U3-G5-PadG5P)") (class "Default")
      (node (ref "U3") (pin "G5P") (pinfunction "G5_G5P") (pintype "bidirectional"))
    )
    (net (code "98") (name "unconnected-(U3-G6-PadG6P)") (class "Default")
      (node (ref "U3") (pin "G6P") (pinfunction "G6_G6P") (pintype "bidirectional"))
    )
    (net (code "99") (name "unconnected-(U3-G7-PadG7P)") (class "Default")
      (node (ref "U3") (pin "G7P") (pinfunction "G7_G7P") (pintype "bidirectional"))
    )
    (net (code "100") (name "unconnected-(U3-G8-PadG8P)") (class "Default")
      (node (ref "U3") (pin "G8P") (pinfunction "G8_G8P") (pintype "bidirectional"))
    )
    (net (code "101") (name "unconnected-(U3-G9-PadG9P)") (class "Default")
      (node (ref "U3") (pin "G9P") (pinfunction "G9_G9P") (pintype "bidirectional"))
    )
    (net (code "102") (name "unconnected-(U3-G18-PadG18P)") (class "Default")
      (node (ref "U3") (pin "G18P") (pinfunction "G18_G18P") (pintype "bidirectional"))
    )
    (net (code "103") (name "unconnected-(U3-G19-PadG19P)") (class "Default")
      (node (ref "U3") (pin "G19P") (pinfunction "G19_G19P") (pintype "bidirectional"))
    )
    (net (code "104") (name "unconnected-(U3-G21-PadG21P)") (class "Default")
      (node (ref "U3") (pin "G21P") (pinfunction "G21_G21P") (pintype "bidirectional"))
    )
    (net (code "105") (name "unconnected-(U3-PadG10)") (class "Default")
      (node (ref "U3") (pin "G10") (pinfunction "G10_G10") (pintype "bidirectional"))
    )
    (net (code "106") (name "unconnected-(U4-INT-Pad6)") (class "Default")
      (node (ref "U4") (pin "6") (pinfunction "INT_6") (pintype "bidirectional"))
    )
    (net (code "107") (name "unconnected-(U4-RST-Pad5)") (class "Default")
      (node (ref "U4") (pin "5") (pinfunction "RST_5") (pintype "bidirectional"))
    )
    (net (code "108") (name "unconnected-(X2-SBU1-PadA8)") (class "Default")
      (node (ref "X2") (pin "A8") (pinfunction "SBU1_A8") (pintype "bidirectional"))
    )
    (net (code "109") (name "unconnected-(X2-SBU2-PadB8)") (class "Default")
      (node (ref "X2") (pin "B8") (pinfunction "SBU2_B8") (pintype "bidirectional"))
    )
    (net (code "110") (name "~{RE}") (class "Default")
      (node (ref "Q1") (pin "3") (pinfunction "C_3") (pintype "passive"))
      (node (ref "R14") (pin "1") (pinfunction "1_1") (pintype "passive"))
      (node (ref "U5") (pin "2") (pinfunction "~{RE}_2") (pintype "input"))
      (node (ref "U5") (pin "3") (pinfunction "DE_3") (pintype "input"))
    )
  )
)
